# PD_Stepper_V1.net
KiCad netlist of a schematic drawn in Altium Designer
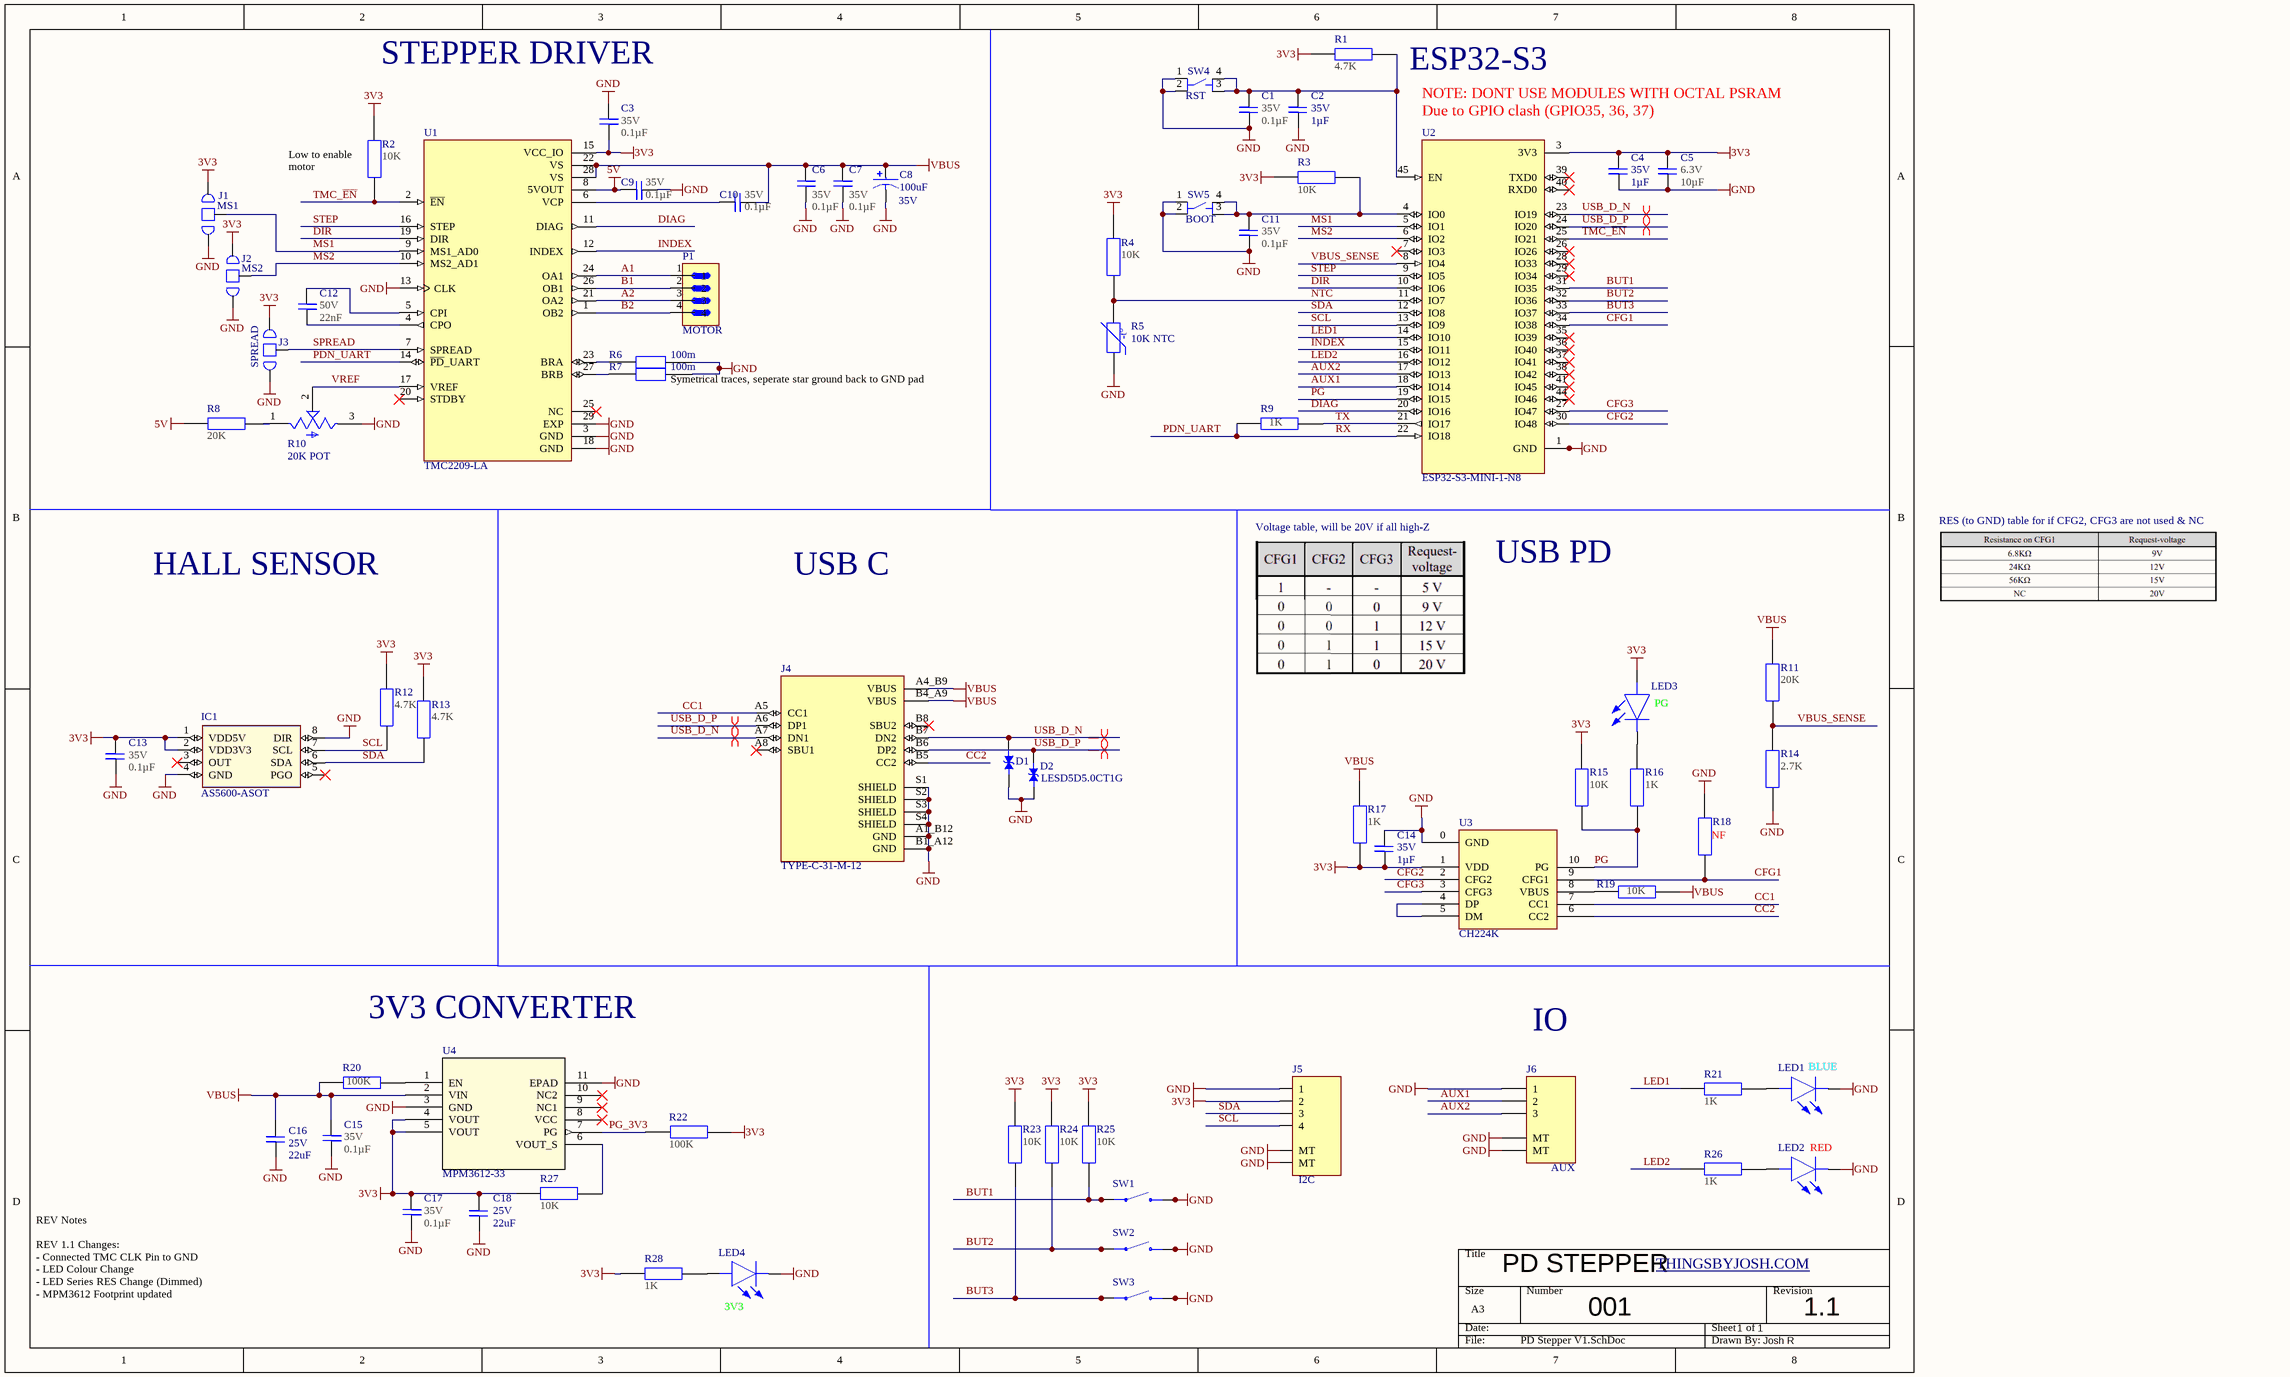
[diagram p0: PD Stepper V1.SchDoc]

(export (version "E")
  (design (tool "Eeschema 10.0.6"))
  (components
    (comp (ref "C1")
      (value "0.1µF")
      (footprint "CAPC1005X55N")
      (description "CAP 0.1µF 35V 0402")
      (fields
        (field (name "MP") "CL05A105KL5NRNC")
        (field (name "MF") "Samsung")
        (field (name "VOLTAGE") "35V")
        (field (name "CHECK_PRICES") "0.1µF")
      )
      (libsource (lib "Custom Library") (part "CL05A105KL5NRNC"))
    )
    (comp (ref "C2")
      (value "1µF ±10% 35V")
      (footprint "CAPC1005X55N")
      (description "CAP 1µF ±10% 35V Ceramic Capacitor X5R 0402 (1005 Metric)")
      (fields
        (field (name "MP") "CL05A105KL5NRNC")
        (field (name "MF") "Samsung")
        (field (name "VOLTAGE") "35V")
        (field (name "CHECK_PRICES") "1µF")
      )
      (libsource (lib "Custom Library") (part "CL05A105KL5NRNC"))
    )
    (comp (ref "C3")
      (value "0.1µF")
      (footprint "CAPC1005X55N")
      (description "CAP 0.1µF 35V 0402")
      (fields
        (field (name "MP") "CL05A105KL5NRNC")
        (field (name "MF") "Samsung")
        (field (name "VOLTAGE") "35V")
        (field (name "CHECK_PRICES") "0.1µF")
      )
      (libsource (lib "Custom Library") (part "CL05A105KL5NRNC"))
    )
    (comp (ref "C4")
      (value "1µF ±10% 35V")
      (footprint "CAPC1005X55N")
      (description "CAP 1µF ±10% 35V Ceramic Capacitor X5R 0402 (1005 Metric)")
      (fields
        (field (name "MP") "CL05A105KL5NRNC")
        (field (name "MF") "Samsung")
        (field (name "VOLTAGE") "35V")
        (field (name "CHECK_PRICES") "1µF")
      )
      (libsource (lib "Custom Library") (part "CL05A105KL5NRNC"))
    )
    (comp (ref "C5")
      (value "10uF 6.3V")
      (footprint "CAPC1005X55N")
      (description "CAP 10µF 6.3V 0402")
      (fields
        (field (name "MP") "CL05A105KL5NRNC")
        (field (name "MF") "Samsung")
        (field (name "VOLTAGE") "6.3V")
        (field (name "CHECK_PRICES") "10µF")
      )
      (libsource (lib "Custom Library") (part "CL05A105KL5NRNC"))
    )
    (comp (ref "C6")
      (value "0.1µF")
      (footprint "CAPC1005X55N")
      (description "CAP 0.1µF 35V 0402")
      (fields
        (field (name "MP") "CL05A105KL5NRNC")
        (field (name "MF") "Samsung")
        (field (name "VOLTAGE") "35V")
        (field (name "CHECK_PRICES") "0.1µF")
      )
      (libsource (lib "Custom Library") (part "CL05A105KL5NRNC"))
    )
    (comp (ref "C7")
      (value "0.1µF")
      (footprint "CAPC1005X55N")
      (description "CAP 0.1µF 35V 0402")
      (fields
        (field (name "MP") "CL05A105KL5NRNC")
        (field (name "MF") "Samsung")
        (field (name "VOLTAGE") "35V")
        (field (name "CHECK_PRICES") "0.1µF")
      )
      (libsource (lib "Custom Library") (part "CL05A105KL5NRNC"))
    )
    (comp (ref "C8")
      (value "100uF")
      (footprint "CAP_EEEFT1V101AP")
      (description "CAP 100µF 35V 260mOhm @ 100kHz 2000 Hrs @ 105°C")
      (fields
        (field (name "MF") "Panasonic")
        (field (name "MP") "EEE-FT1V101AP")
        (field (name "VOLTAGE") "35V")
      )
      (libsource (lib "Custom Library") (part "EEEFT1V101AP"))
    )
    (comp (ref "C9")
      (value "0.1µF")
      (footprint "CAPC1005X55N")
      (description "CAP 0.1µF 35V 0402")
      (fields
        (field (name "MP") "CL05A105KL5NRNC")
        (field (name "MF") "Samsung")
        (field (name "VOLTAGE") "35V")
        (field (name "CHECK_PRICES") "0.1µF")
      )
      (libsource (lib "Custom Library") (part "CL05A105KL5NRNC"))
    )
    (comp (ref "C10")
      (value "0.1µF")
      (footprint "CAPC1005X55N")
      (description "CAP 0.1µF 35V 0402")
      (fields
        (field (name "MP") "CL05A105KL5NRNC")
        (field (name "MF") "Samsung")
        (field (name "VOLTAGE") "35V")
        (field (name "CHECK_PRICES") "0.1µF")
      )
      (libsource (lib "Custom Library") (part "CL05A105KL5NRNC"))
    )
    (comp (ref "C11")
      (value "0.1µF")
      (footprint "CAPC1005X55N")
      (description "CAP 0.1µF 35V 0402")
      (fields
        (field (name "MP") "CL05A105KL5NRNC")
        (field (name "MF") "Samsung")
        (field (name "VOLTAGE") "35V")
        (field (name "CHECK_PRICES") "0.1µF")
      )
      (libsource (lib "Custom Library") (part "CL05A105KL5NRNC"))
    )
    (comp (ref "C12")
      (value "22nF")
      (footprint "CAPC1005X55N")
      (description "CAP 22nF 50V 0402")
      (fields
        (field (name "MP") "CL05A105KL5NRNC")
        (field (name "MF") "Samsung")
        (field (name "VOLTAGE") "50V")
        (field (name "CHECK_PRICES") "22nF")
      )
      (libsource (lib "Custom Library") (part "CL05A105KL5NRNC"))
    )
    (comp (ref "C13")
      (value "0.1µF")
      (footprint "CAPC1005X55N")
      (description "CAP 0.1µF 35V 0402")
      (fields
        (field (name "MP") "CL05A105KL5NRNC")
        (field (name "MF") "Samsung")
        (field (name "VOLTAGE") "35V")
        (field (name "CHECK_PRICES") "0.1µF")
      )
      (libsource (lib "Custom Library") (part "CL05A105KL5NRNC"))
    )
    (comp (ref "C14")
      (value "1µF ±10% 35V")
      (footprint "CAPC1005X55N")
      (description "CAP 1µF ±10% 35V Ceramic Capacitor X5R 0402 (1005 Metric)")
      (fields
        (field (name "MP") "CL05A105KL5NRNC")
        (field (name "MF") "Samsung")
        (field (name "VOLTAGE") "35V")
        (field (name "CHECK_PRICES") "1µF")
      )
      (libsource (lib "Custom Library") (part "CL05A105KL5NRNC"))
    )
    (comp (ref "C15")
      (value "0.1µF")
      (footprint "CAPC1005X55N")
      (description "CAP 0.1µF 35V 0402")
      (fields
        (field (name "MP") "CL05A105KL5NRNC")
        (field (name "MF") "Samsung")
        (field (name "VOLTAGE") "35V")
        (field (name "CHECK_PRICES") "0.1µF")
      )
      (libsource (lib "Custom Library") (part "CL05A105KL5NRNC"))
    )
    (comp (ref "C16")
      (value "22uF")
      (footprint "CAPC2012X135N")
      (description "CAP 22uF 25V")
      (fields
        (field (name "MP") "GRM21BR61E226ME44K")
        (field (name "MF") "Murata Electronics")
        (field (name "VOLTAGE") "25V")
      )
      (libsource (lib "Custom Library") (part "GRM21BR61E226ME44K"))
    )
    (comp (ref "C17")
      (value "0.1µF")
      (footprint "CAPC1005X55N")
      (description "CAP 0.1µF 35V 0402")
      (fields
        (field (name "MP") "CL05A105KL5NRNC")
        (field (name "MF") "Samsung")
        (field (name "VOLTAGE") "35V")
        (field (name "CHECK_PRICES") "0.1µF")
      )
      (libsource (lib "Custom Library") (part "CL05A105KL5NRNC"))
    )
    (comp (ref "C18")
      (value "22uF")
      (footprint "CAPC2012X135N")
      (description "CAP 22uF 25V")
      (fields
        (field (name "MP") "GRM21BR61E226ME44K")
        (field (name "MF") "Murata Electronics")
        (field (name "VOLTAGE") "25V")
      )
      (libsource (lib "Custom Library") (part "GRM21BR61E226ME44K"))
    )
    (comp (ref "D1")
      (value "LESD5D5.0CT1G")
      (footprint "TVS_LESD5D5.0CT1G")
      (description "Transient Voltage Suppressors for ESD Protection")
      (fields (field (name "MF") "Leshan Radio Co."))
      (libsource (lib "Custom Library") (part "LESD5D5.0CT1G"))
    )
    (comp (ref "D2")
      (value "LESD5D5.0CT1G")
      (footprint "TVS_LESD5D5.0CT1G")
      (description "Transient Voltage Suppressors for ESD Protection")
      (fields (field (name "MF") "Leshan Radio Co."))
      (libsource (lib "Custom Library") (part "LESD5D5.0CT1G"))
    )
    (comp (ref "IC1")
      (value "AS5600-ASOT")
      (footprint "SOIC127P600X175-8N")
      (description "Hall Effect Sensor Angle External Magnet, Not Included Gull Wing")
      (fields (field (name "MF") "ams"))
      (libsource (lib "Custom Library") (part "AS5600-ASOT"))
    )
    (comp (ref "J1")
      (value "MS1")
      (footprint "3 way solder jumper")
      (libsource (lib "Custom Library") (part "3 Way Solder Jumper"))
    )
    (comp (ref "J2")
      (value "MS2")
      (footprint "3 way solder jumper")
      (libsource (lib "Custom Library") (part "3 Way Solder Jumper"))
    )
    (comp (ref "J3")
      (value "SPREAD")
      (footprint "3 way solder jumper")
      (libsource (lib "Custom Library") (part "3 Way Solder Jumper"))
    )
    (comp (ref "J4")
      (value "TYPE-C-31-M-12")
      (footprint "HRO_TYPE-C-31-M-12")
      (description "USB Connectors 24 Receptacle 1 8.94*7.3mm RoHS")
      (fields (field (name "MF") "HRO Electronics Co., Ltd."))
      (libsource (lib "Custom Library") (part "TYPE-C-31-M-12"))
    )
    (comp (ref "J5")
      (value "I2C")
      (footprint "JST_SM04B-SRSS-TB(LF)(SN)")
      (description "SH Series 1.0 mm Pitch 2 Position Single Row Side Entry Shrouded Header")
      (fields (field (name "MP") "SM04B-SRSS-TB(LF)(SN)") (field (name "Comment") "JST SH 4P"))
      (libsource (lib "Custom Library") (part "SM04B-SRSS-TB(LF)(SN)"))
    )
    (comp (ref "J6")
      (value "AUX")
      (footprint "JST_SM03B-SRSS-TB(LF)(SN)")
      (description "Connector Header Surface Mount, Right Angle 3 position 0.039 _1.00mm_")
      (fields (field (name "MP") "SM03B-SRSS-TB_LF__SN_") (field (name "MF") "JST Sales"))
      (libsource (lib "Custom Library") (part "SM03B-SRSS-TB(LF)(SN)"))
    )
    (comp (ref "LED1")
      (value "LED BLUE")
      (footprint "LEDC1608X80N")
      (description "BLUE LED Indication - 0603 (1608 Metric)")
      (fields (field (name "MF") "Wurth Electronics") (field (name "MP") "150060GS75000"))
      (libsource (lib "Custom Library") (part "150060GS75000"))
    )
    (comp (ref "LED2")
      (value "LED RED")
      (footprint "LEDC1608X80N")
      (description "RED LED Indication - 0603 (1608 Metric)")
      (fields (field (name "MF") "Wurth Electronics"))
      (libsource (lib "Custom Library") (part "150060GS75000"))
    )
    (comp (ref "LED3")
      (value "LED GREEN")
      (footprint "LEDC1608X80N")
      (description "Green 520nm LED Indication - Discrete 3.2V 0603 (1608 Metric)")
      (fields (field (name "MF") "Wurth Electronics") (field (name "MP") "150060GS75000"))
      (libsource (lib "Custom Library") (part "150060GS75000"))
    )
    (comp (ref "LED4")
      (value "LED GREEN")
      (footprint "LEDC1608X80N")
      (description "Green 520nm LED Indication - Discrete 3.2V 0603 (1608 Metric)")
      (fields (field (name "MF") "Wurth Electronics") (field (name "MP") "150060GS75000"))
      (libsource (lib "Custom Library") (part "150060GS75000"))
    )
    (comp (ref "P1")
      (value "MOTOR")
      (footprint "JST_S4B-PH-SM4-TB")
      (description "Connector Header Surface Mount, Right Angle 4 position 0.079 _2.00mm_")
      (fields (field (name "MF") "JST Sales") (field (name "MP") "S4B-PH-SM4-TB"))
      (libsource (lib "Custom Library") (part "S4B-PH-SM4-TB"))
    )
    (comp (ref "R1")
      (value "4.7K")
      (footprint "RESC1005X37N")
      (description "RES 4.7K 0402")
      (fields (field (name "MP") "AC0402JR-0724KL"))
      (libsource (lib "Custom Library") (part "AC0402JR-0724KL"))
    )
    (comp (ref "R2")
      (value "10K")
      (footprint "RESC1005X37N")
      (description "RES 10K 0402")
      (fields (field (name "MP") "AC0402JR-0724KL"))
      (libsource (lib "Custom Library") (part "AC0402JR-0724KL"))
    )
    (comp (ref "R3")
      (value "10K")
      (footprint "RESC1005X37N")
      (description "RES 10K 0402")
      (fields (field (name "MP") "AC0402JR-0724KL"))
      (libsource (lib "Custom Library") (part "AC0402JR-0724KL"))
    )
    (comp (ref "R4")
      (value "10K")
      (footprint "RESC1005X37N")
      (description "RES 10K 0402")
      (fields (field (name "MP") "AC0402JR-0724KL"))
      (libsource (lib "Custom Library") (part "AC0402JR-0724KL"))
    )
    (comp (ref "R5")
      (value "10K NTC")
      (footprint "NTC Pads")
      (description "NTC 10K")
      (libsource (lib "Custom Library") (part "NTC"))
    )
    (comp (ref "R6")
      (value "100m")
      (footprint "RESC3216X89N")
      (description "Res Metal Foil 1206 100m Ohm 1% 1W Â±100ppm/Â°C Molded SMD Paper T/R")
      (fields (field (name "MP") "PE1206FRF470R1L"))
      (libsource (lib "Custom Library") (part "PE1206FRF470R1L"))
    )
    (comp (ref "R7")
      (value "100m")
      (footprint "RESC3216X89N")
      (description "Res Metal Foil 1206 100m Ohm 1% 1W Â±100ppm/Â°C Molded SMD Paper T/R")
      (fields (field (name "MP") "PE1206FRF470R1L"))
      (libsource (lib "Custom Library") (part "PE1206FRF470R1L"))
    )
    (comp (ref "R8")
      (value "20K")
      (footprint "RESC1005X37N")
      (description "RES 20K 0402")
      (fields (field (name "MP") "AC0402JR-0724KL"))
      (libsource (lib "Custom Library") (part "AC0402JR-0724KL"))
    )
    (comp (ref "R9")
      (value "1K")
      (footprint "RESC1005X37N")
      (description "RES 1K 0402")
      (fields (field (name "MP") "AC0402JR-0724KL"))
      (libsource (lib "Custom Library") (part "AC0402JR-0724KL"))
    )
    (comp (ref "R10")
      (value "20K POT")
      (footprint "TRIM_TC33X-2-203E")
      (description "20k Ohms 0.1W, 1/10W J Lead Surface Mount Trimmer Potentiometer Cermet 1 Turn Top Adjustment")
      (fields (field (name "MF") "Bourns") (field (name "DIGI-KEY_PART_NUMBER") "TC33X-2-203ECT-ND"))
      (libsource (lib "Custom Library") (part "TC33X-2-203E"))
    )
    (comp (ref "R11")
      (value "20K")
      (footprint "RESC1005X37N")
      (description "RES 20K 0402")
      (fields (field (name "MP") "AC0402JR-0724KL"))
      (libsource (lib "Custom Library") (part "AC0402JR-0724KL"))
    )
    (comp (ref "R12")
      (value "4.7K")
      (footprint "RESC1005X37N")
      (description "RES 4.7K 0402")
      (fields (field (name "MP") "AC0402JR-0724KL"))
      (libsource (lib "Custom Library") (part "AC0402JR-0724KL"))
    )
    (comp (ref "R13")
      (value "4.7K")
      (footprint "RESC1005X37N")
      (description "RES 4.7K 0402")
      (fields (field (name "MP") "AC0402JR-0724KL"))
      (libsource (lib "Custom Library") (part "AC0402JR-0724KL"))
    )
    (comp (ref "R14")
      (value "2.7K")
      (footprint "RESC1005X37N")
      (description "RES 2.7K 0402")
      (fields (field (name "MP") "AC0402JR-0724KL"))
      (libsource (lib "Custom Library") (part "AC0402JR-0724KL"))
    )
    (comp (ref "R15")
      (value "10K")
      (footprint "RESC1005X37N")
      (description "RES 10K 0402")
      (fields (field (name "MP") "AC0402JR-0724KL"))
      (libsource (lib "Custom Library") (part "AC0402JR-0724KL"))
    )
    (comp (ref "R16")
      (value "1K")
      (footprint "RESC1005X37N")
      (description "RES 1K 0402")
      (fields (field (name "MP") "AC0402JR-0724KL"))
      (libsource (lib "Custom Library") (part "AC0402JR-0724KL"))
    )
    (comp (ref "R17")
      (value "1K")
      (footprint "RESC1005X37N")
      (description "RES 1K 0402")
      (fields (field (name "MP") "AC0402JR-0724KL"))
      (libsource (lib "Custom Library") (part "AC0402JR-0724KL"))
    )
    (comp (ref "R18")
      (value "NF")
      (footprint "RESC1005X37N")
      (description "RES NC")
      (fields (field (name "MP") "AC0402JR-0724KL"))
      (libsource (lib "Custom Library") (part "AC0402JR-0724KL"))
    )
    (comp (ref "R19")
      (value "10K")
      (footprint "RESC1005X37N")
      (description "RES 10K 0402")
      (fields (field (name "MP") "AC0402JR-0724KL"))
      (libsource (lib "Custom Library") (part "AC0402JR-0724KL"))
    )
    (comp (ref "R20")
      (value "100K")
      (footprint "RESC1005X37N")
      (description "RES 100K 0402")
      (fields (field (name "MP") "AC0402JR-0724KL"))
      (libsource (lib "Custom Library") (part "AC0402JR-0724KL"))
    )
    (comp (ref "R21")
      (value "1K")
      (footprint "RESC1005X37N")
      (description "RES 1K 0402")
      (fields (field (name "MP") "AC0402JR-0724KL"))
      (libsource (lib "Custom Library") (part "AC0402JR-0724KL"))
    )
    (comp (ref "R22")
      (value "100K")
      (footprint "RESC1005X37N")
      (description "RES 100K 0402")
      (fields (field (name "MP") "AC0402JR-0724KL"))
      (libsource (lib "Custom Library") (part "AC0402JR-0724KL"))
    )
    (comp (ref "R23")
      (value "10K")
      (footprint "RESC1005X37N")
      (description "RES 10K 0402")
      (fields (field (name "MP") "AC0402JR-0724KL"))
      (libsource (lib "Custom Library") (part "AC0402JR-0724KL"))
    )
    (comp (ref "R24")
      (value "10K")
      (footprint "RESC1005X37N")
      (description "RES 10K 0402")
      (fields (field (name "MP") "AC0402JR-0724KL"))
      (libsource (lib "Custom Library") (part "AC0402JR-0724KL"))
    )
    (comp (ref "R25")
      (value "10K")
      (footprint "RESC1005X37N")
      (description "RES 10K 0402")
      (fields (field (name "MP") "AC0402JR-0724KL"))
      (libsource (lib "Custom Library") (part "AC0402JR-0724KL"))
    )
    (comp (ref "R26")
      (value "1K")
      (footprint "RESC1005X37N")
      (description "RES 1K 0402")
      (fields (field (name "MP") "AC0402JR-0724KL"))
      (libsource (lib "Custom Library") (part "AC0402JR-0724KL"))
    )
    (comp (ref "R27")
      (value "10K")
      (footprint "RESC1005X37N")
      (description "RES 10K 0402")
      (fields (field (name "MP") "AC0402JR-0724KL"))
      (libsource (lib "Custom Library") (part "AC0402JR-0724KL"))
    )
    (comp (ref "R28")
      (value "1K")
      (footprint "RESC1005X37N")
      (description "RES 1K 0402")
      (fields (field (name "MP") "AC0402JR-0724KL"))
      (libsource (lib "Custom Library") (part "AC0402JR-0724KL"))
    )
    (comp (ref "SW1")
      (value "EVQ-P7J01P")
      (footprint "SW_EVQ-P7J01P")
      (description "Tactile Switch SPST-NO Side Actuated Surface Mount, Right Angle")
      (fields (field (name "MF") "Panasonic Electronic"))
      (libsource (lib "Custom Library") (part "EVQ-P7J01P"))
    )
    (comp (ref "SW2")
      (value "EVQ-P7J01P")
      (footprint "SW_EVQ-P7J01P")
      (description "Tactile Switch SPST-NO Side Actuated Surface Mount, Right Angle")
      (fields (field (name "MF") "Panasonic Electronic"))
      (libsource (lib "Custom Library") (part "EVQ-P7J01P"))
    )
    (comp (ref "SW3")
      (value "EVQ-P7J01P")
      (footprint "SW_EVQ-P7J01P")
      (description "Tactile Switch SPST-NO Side Actuated Surface Mount, Right Angle")
      (fields (field (name "MF") "Panasonic Electronic"))
      (libsource (lib "Custom Library") (part "EVQ-P7J01P"))
    )
    (comp (ref "SW4")
      (value "PTS810_SJM_250_SMTR_LFS")
      (footprint "SW_PTS810_SJM_250_SMTR_LFS")
      (description "Tactile Switch SPST-NO Top Actuated Surface Mount")
      (fields (field (name "MF") "C&K") (field (name "MP") "PTS810 SJM 250 SMTR LFS"))
      (libsource (lib "Custom Library") (part "PTS810_SJM_250_SMTR_LFS"))
    )
    (comp (ref "SW5")
      (value "PTS810_SJM_250_SMTR_LFS")
      (footprint "SW_PTS810_SJM_250_SMTR_LFS")
      (description "Tactile Switch SPST-NO Top Actuated Surface Mount")
      (fields (field (name "MF") "C&K") (field (name "MP") "PTS810 SJM 250 SMTR LFS"))
      (libsource (lib "Custom Library") (part "PTS810_SJM_250_SMTR_LFS"))
    )
    (comp (ref "U1")
      (value "TMC2209-LA")
      (footprint "QFN50P500X500X90-29N")
      (fields (field (name "MF") "Trinamic"))
      (libsource (lib "Custom Library") (part "TMC2209-LA"))
    )
    (comp (ref "U2")
      (value "ESP32-S3-MINI-1-N8")
      (footprint "XCVR_ESP32-S3-MINI-1-N8")
      (description "Bluetooth, WiFi 802.11b/g/n, Bluetooth v5.0 Transceiver Module 2.4GHz PCB Trace Surface Mount")
      (fields (field (name "MF") "Espressif Systems"))
      (libsource (lib "Custom Library") (part "ESP32-S3-MINI-1-N8"))
    )
    (comp (ref "U3")
      (value "CH224K")
      (footprint "ESSOP-10")
      (description "USB PD Sink Controller")
      (libsource (lib "Custom Library") (part "CH224K"))
    )
    (comp (ref "U4")
      (value "MPM3612-33")
      (footprint "LGA_MPM3612_MNP")
      (libsource (lib "Custom Library") (part "MPM3612-33"))
    )
  )
  (nets
    (net (code "1") (name "/A1") (class "Default")
      (node (ref "P1") (pin "1") (pinfunction "1_1") (pintype "passive"))
      (node (ref "U1") (pin "24") (pinfunction "OA1_24") (pintype "output"))
    )
    (net (code "2") (name "/A2") (class "Default")
      (node (ref "P1") (pin "3") (pinfunction "3_3") (pintype "passive"))
      (node (ref "U1") (pin "21") (pinfunction "OA2_21") (pintype "output"))
    )
    (net (code "3") (name "/AUX1") (class "Default")
      (node (ref "J6") (pin "2") (pinfunction "2_2") (pintype "passive"))
      (node (ref "U2") (pin "18") (pinfunction "IO14_18") (pintype "bidirectional"))
    )
    (net (code "4") (name "/AUX2") (class "Default")
      (node (ref "J6") (pin "3") (pinfunction "3_3") (pintype "passive"))
      (node (ref "U2") (pin "17") (pinfunction "IO13_17") (pintype "bidirectional"))
    )
    (net (code "5") (name "/B1") (class "Default")
      (node (ref "P1") (pin "2") (pinfunction "2_2") (pintype "passive"))
      (node (ref "U1") (pin "26") (pinfunction "OB1_26") (pintype "output"))
    )
    (net (code "6") (name "/B2") (class "Default")
      (node (ref "P1") (pin "4") (pinfunction "4_4") (pintype "passive"))
      (node (ref "U1") (pin "1") (pinfunction "OB2_1") (pintype "output"))
    )
    (net (code "7") (name "/BUT1") (class "Default")
      (node (ref "R25") (pin "1") (pinfunction "1_1") (pintype "passive"))
      (node (ref "SW1") (pin "1_1") (pinfunction "1_1_1") (pintype "passive"))
      (node (ref "SW1") (pin "1_2") (pinfunction "1_1_2") (pintype "passive"))
      (node (ref "U2") (pin "31") (pinfunction "IO35_31") (pintype "bidirectional"))
    )
    (net (code "8") (name "/BUT2") (class "Default")
      (node (ref "R24") (pin "1") (pinfunction "1_1") (pintype "passive"))
      (node (ref "SW2") (pin "1_1") (pinfunction "1_1_1") (pintype "passive"))
      (node (ref "SW2") (pin "1_2") (pinfunction "1_1_2") (pintype "passive"))
      (node (ref "U2") (pin "32") (pinfunction "IO36_32") (pintype "bidirectional"))
    )
    (net (code "9") (name "/BUT3") (class "Default")
      (node (ref "R23") (pin "1") (pinfunction "1_1") (pintype "passive"))
      (node (ref "SW3") (pin "1_1") (pinfunction "1_1_1") (pintype "passive"))
      (node (ref "SW3") (pin "1_2") (pinfunction "1_1_2") (pintype "passive"))
      (node (ref "U2") (pin "33") (pinfunction "IO37_33") (pintype "bidirectional"))
    )
    (net (code "10") (name "/CC1") (class "Default")
      (node (ref "J4") (pin "A5") (pinfunction "CC1_A5") (pintype "bidirectional"))
      (node (ref "U3") (pin "7") (pinfunction "CC1_7") (pintype "passive"))
    )
    (net (code "11") (name "/CC2") (class "Default")
      (node (ref "J4") (pin "B5") (pinfunction "CC2_B5") (pintype "bidirectional"))
      (node (ref "U3") (pin "6") (pinfunction "CC2_6") (pintype "passive"))
    )
    (net (code "12") (name "/CFG1") (class "Default")
      (node (ref "R18") (pin "1") (pinfunction "1_1") (pintype "passive"))
      (node (ref "U2") (pin "34") (pinfunction "IO38_34") (pintype "bidirectional"))
      (node (ref "U3") (pin "9") (pinfunction "CFG1_9") (pintype "passive"))
    )
    (net (code "13") (name "/CFG2") (class "Default")
      (node (ref "U2") (pin "30") (pinfunction "IO48_30") (pintype "bidirectional"))
      (node (ref "U3") (pin "2") (pinfunction "CFG2_2") (pintype "passive"))
    )
    (net (code "14") (name "/CFG3") (class "Default")
      (node (ref "U2") (pin "27") (pinfunction "IO47_27") (pintype "bidirectional"))
      (node (ref "U3") (pin "3") (pinfunction "CFG3_3") (pintype "passive"))
    )
    (net (code "15") (name "/DIAG") (class "Default")
      (node (ref "U1") (pin "11") (pinfunction "DIAG_11") (pintype "output"))
      (node (ref "U2") (pin "20") (pinfunction "IO16_20") (pintype "bidirectional"))
    )
    (net (code "16") (name "/DIR") (class "Default")
      (node (ref "U1") (pin "19") (pinfunction "DIR_19") (pintype "input"))
      (node (ref "U2") (pin "10") (pinfunction "IO6_10") (pintype "bidirectional"))
    )
    (net (code "17") (name "/INDEX") (class "Default")
      (node (ref "U1") (pin "12") (pinfunction "INDEX_12") (pintype "output"))
      (node (ref "U2") (pin "15") (pinfunction "IO11_15") (pintype "bidirectional"))
    )
    (net (code "18") (name "/LED1") (class "Default")
      (node (ref "R21") (pin "2") (pinfunction "2_2") (pintype "passive"))
      (node (ref "U2") (pin "14") (pinfunction "IO10_14") (pintype "bidirectional"))
    )
    (net (code "19") (name "/LED2") (class "Default")
      (node (ref "R26") (pin "2") (pinfunction "2_2") (pintype "passive"))
      (node (ref "U2") (pin "16") (pinfunction "IO12_16") (pintype "bidirectional"))
    )
    (net (code "20") (name "/MS1") (class "Default")
      (node (ref "J1") (pin "2") (pinfunction "2_2") (pintype "passive"))
      (node (ref "U1") (pin "9") (pinfunction "MS1_AD0_9") (pintype "input"))
      (node (ref "U2") (pin "5") (pinfunction "IO1_5") (pintype "bidirectional"))
    )
    (net (code "21") (name "/MS2") (class "Default")
      (node (ref "J2") (pin "2") (pinfunction "2_2") (pintype "passive"))
      (node (ref "U1") (pin "10") (pinfunction "MS2_AD1_10") (pintype "input"))
      (node (ref "U2") (pin "6") (pinfunction "IO2_6") (pintype "bidirectional"))
    )
    (net (code "22") (name "/NTC") (class "Default")
      (node (ref "R4") (pin "2") (pinfunction "2_2") (pintype "passive"))
      (node (ref "R5") (pin "2") (pinfunction "2_2") (pintype "passive"))
      (node (ref "U2") (pin "11") (pinfunction "IO7_11") (pintype "bidirectional"))
    )
    (net (code "23") (name "/PDN_UART") (class "Default")
      (node (ref "R9") (pin "2") (pinfunction "2_2") (pintype "passive"))
      (node (ref "U1") (pin "14") (pinfunction "~{PD}_UART_14") (pintype "bidirectional"))
      (node (ref "U2") (pin "22") (pinfunction "IO18_22") (pintype "input"))
    )
    (net (code "24") (name "/PG") (class "Default")
      (node (ref "R15") (pin "1") (pinfunction "1_1") (pintype "passive"))
      (node (ref "R16") (pin "1") (pinfunction "1_1") (pintype "passive"))
      (node (ref "U2") (pin "19") (pinfunction "IO15_19") (pintype "bidirectional"))
      (node (ref "U3") (pin "10") (pinfunction "PG_10") (pintype "passive"))
    )
    (net (code "25") (name "/PG_3V3") (class "Default")
      (node (ref "R22") (pin "1") (pinfunction "1_1") (pintype "passive"))
      (node (ref "U4") (pin "7") (pinfunction "PG_7") (pintype "output"))
    )
    (net (code "26") (name "/SCL") (class "Default")
      (node (ref "IC1") (pin "7") (pinfunction "SCL_7") (pintype "bidirectional"))
      (node (ref "J5") (pin "4") (pinfunction "4_4") (pintype "passive"))
      (node (ref "R12") (pin "1") (pinfunction "1_1") (pintype "passive"))
      (node (ref "U2") (pin "13") (pinfunction "IO9_13") (pintype "bidirectional"))
    )
    (net (code "27") (name "/SDA") (class "Default")
      (node (ref "IC1") (pin "6") (pinfunction "SDA_6") (pintype "bidirectional"))
      (node (ref "J5") (pin "3") (pinfunction "3_3") (pintype "passive"))
      (node (ref "R13") (pin "1") (pinfunction "1_1") (pintype "passive"))
      (node (ref "U2") (pin "12") (pinfunction "IO8_12") (pintype "bidirectional"))
    )
    (net (code "28") (name "/SPREAD") (class "Default")
      (node (ref "J3") (pin "2") (pinfunction "2_2") (pintype "passive"))
      (node (ref "U1") (pin "7") (pinfunction "SPREAD_7") (pintype "input"))
    )
    (net (code "29") (name "/STEP") (class "Default")
      (node (ref "U1") (pin "16") (pinfunction "STEP_16") (pintype "input"))
      (node (ref "U2") (pin "9") (pinfunction "IO5_9") (pintype "bidirectional"))
    )
    (net (code "30") (name "/TMC_~{EN}") (class "Default")
      (node (ref "R2") (pin "1") (pinfunction "1_1") (pintype "passive"))
      (node (ref "U1") (pin "2") (pinfunction "~{EN}_2") (pintype "input"))
      (node (ref "U2") (pin "25") (pinfunction "IO21_25") (pintype "bidirectional"))
    )
    (net (code "31") (name "/TX") (class "Default")
      (node (ref "R9") (pin "1") (pinfunction "1_1") (pintype "passive"))
      (node (ref "U2") (pin "21") (pinfunction "IO17_21") (pintype "output"))
    )
    (net (code "32") (name "/USB_D_N") (class "Default")
      (node (ref "D1") (pin "2") (pinfunction "2_2") (pintype "passive"))
      (node (ref "J4") (pin "A7") (pinfunction "DN1_A7") (pintype "bidirectional"))
      (node (ref "J4") (pin "B7") (pinfunction "DN2_B7") (pintype "bidirectional"))
      (node (ref "U2") (pin "23") (pinfunction "IO19_23") (pintype "bidirectional"))
    )
    (net (code "33") (name "/USB_D_P") (class "Default")
      (node (ref "D2") (pin "2") (pinfunction "2_2") (pintype "passive"))
      (node (ref "J4") (pin "A6") (pinfunction "DP1_A6") (pintype "bidirectional"))
      (node (ref "J4") (pin "B6") (pinfunction "DP2_B6") (pintype "bidirectional"))
      (node (ref "U2") (pin "24") (pinfunction "IO20_24") (pintype "bidirectional"))
    )
    (net (code "34") (name "/VBUS_SENSE") (class "Default")
      (node (ref "R11") (pin "1") (pinfunction "1_1") (pintype "passive"))
      (node (ref "R14") (pin "2") (pinfunction "2_2") (pintype "passive"))
      (node (ref "U2") (pin "8") (pinfunction "IO4_8") (pintype "input"))
    )
    (net (code "35") (name "/VREF") (class "Default")
      (node (ref "R10") (pin "2") (pinfunction "W_2") (pintype "passive"))
      (node (ref "U1") (pin "17") (pinfunction "VREF_17") (pintype "input"))
    )
    (net (code "36") (name "3V3") (class "Default")
      (node (ref "C13") (pin "1") (pinfunction "1_1") (pintype "passive"))
      (node (ref "C14") (pin "2") (pinfunction "2_2") (pintype "passive"))
      (node (ref "C17") (pin "2") (pinfunction "2_2") (pintype "passive"))
      (node (ref "C18") (pin "1") (pinfunction "1_1") (pintype "passive"))
      (node (ref "C3") (pin "1") (pinfunction "1_1") (pintype "passive"))
      (node (ref "C4") (pin "1") (pinfunction "1_1") (pintype "passive"))
      (node (ref "C5") (pin "1") (pinfunction "1_1") (pintype "passive"))
      (node (ref "IC1") (pin "1") (pinfunction "VDD5V_1") (pintype "bidirectional"))
      (node (ref "IC1") (pin "2") (pinfunction "VDD3V3_2") (pintype "bidirectional"))
      (node (ref "J1") (pin "1") (pinfunction "12_1") (pintype "passive"))
      (node (ref "J2") (pin "1") (pinfunction "12_1") (pintype "passive"))
      (node (ref "J3") (pin "1") (pinfunction "12_1") (pintype "passive"))
      (node (ref "J5") (pin "2") (pinfunction "2_2") (pintype "passive"))
      (node (ref "LED3") (pin "2") (pinfunction "A_2") (pintype "passive"))
      (node (ref "R1") (pin "2") (pinfunction "2_2") (pintype "passive"))
      (node (ref "R12") (pin "2") (pinfunction "2_2") (pintype "passive"))
      (node (ref "R13") (pin "2") (pinfunction "2_2") (pintype "passive"))
      (node (ref "R15") (pin "2") (pinfunction "2_2") (pintype "passive"))
      (node (ref "R17") (pin "1") (pinfunction "1_1") (pintype "passive"))
      (node (ref "R2") (pin "2") (pinfunction "2_2") (pintype "passive"))
      (node (ref "R22") (pin "2") (pinfunction "2_2") (pintype "passive"))
      (node (ref "R23") (pin "2") (pinfunction "2_2") (pintype "passive"))
      (node (ref "R24") (pin "2") (pinfunction "2_2") (pintype "passive"))
      (node (ref "R25") (pin "2") (pinfunction "2_2") (pintype "passive"))
      (node (ref "R27") (pin "2") (pinfunction "2_2") (pintype "passive"))
      (node (ref "R28") (pin "2") (pinfunction "2_2") (pintype "passive"))
      (node (ref "R3") (pin "2") (pinfunction "2_2") (pintype "passive"))
      (node (ref "R4") (pin "1") (pinfunction "1_1") (pintype "passive"))
      (node (ref "U1") (pin "15") (pinfunction "VCC_IO_15") (pintype "power_in"))
      (node (ref "U2") (pin "3") (pinfunction "3V3_3") (pintype "power_in"))
      (node (ref "U3") (pin "1") (pinfunction "VDD_1") (pintype "passive"))
      (node (ref "U4") (pin "4") (pinfunction "VOUT_4") (pintype "power_in"))
      (node (ref "U4") (pin "5") (pinfunction "VOUT_5") (pintype "power_in"))
    )
    (net (code "37") (name "5V") (class "Default")
      (node (ref "C9") (pin "1") (pinfunction "1_1") (pintype "passive"))
      (node (ref "R8") (pin "2") (pinfunction "2_2") (pintype "passive"))
      (node (ref "U1") (pin "8") (pinfunction "5VOUT_8") (pintype "power_in"))
    )
    (net (code "38") (name "GND") (class "Default")
      (node (ref "C1") (pin "2") (pinfunction "2_2") (pintype "passive"))
      (node (ref "C11") (pin "2") (pinfunction "2_2") (pintype "passive"))
      (node (ref "C13") (pin "2") (pinfunction "2_2") (pintype "passive"))
      (node (ref "C14") (pin "1") (pinfunction "1_1") (pintype "passive"))
      (node (ref "C15") (pin "1") (pinfunction "1_1") (pintype "passive"))
      (node (ref "C16") (pin "2") (pinfunction "2_2") (pintype "passive"))
      (node (ref "C17") (pin "1") (pinfunction "1_1") (pintype "passive"))
      (node (ref "C18") (pin "2") (pinfunction "2_2") (pintype "passive"))
      (node (ref "C2") (pin "2") (pinfunction "2_2") (pintype "passive"))
      (node (ref "C3") (pin "2") (pinfunction "2_2") (pintype "passive"))
      (node (ref "C4") (pin "2") (pinfunction "2_2") (pintype "passive"))
      (node (ref "C5") (pin "2") (pinfunction "2_2") (pintype "passive"))
      (node (ref "C6") (pin "1") (pinfunction "1_1") (pintype "passive"))
      (node (ref "C7") (pin "1") (pinfunction "1_1") (pintype "passive"))
      (node (ref "C8") (pin "2") (pinfunction "2_2") (pintype "passive"))
      (node (ref "C9") (pin "2") (pinfunction "2_2") (pintype "passive"))
      (node (ref "D1") (pin "1") (pinfunction "1_1") (pintype "passive"))
      (node (ref "D2") (pin "1") (pinfunction "1_1") (pintype "passive"))
      (node (ref "IC1") (pin "4") (pinfunction "GND_4") (pintype "bidirectional"))
      (node (ref "IC1") (pin "8") (pinfunction "DIR_8") (pintype "bidirectional"))
      (node (ref "J1") (pin "3") (pinfunction "3_3") (pintype "passive"))
      (node (ref "J2") (pin "3") (pinfunction "3_3") (pintype "passive"))
      (node (ref "J3") (pin "3") (pinfunction "3_3") (pintype "passive"))
      (node (ref "J4") (pin "A1_B12") (pinfunction "GND_A1_B12") (pintype "power_in"))
      (node (ref "J4") (pin "B1_A12") (pinfunction "GND_B1_A12") (pintype "power_in"))
      (node (ref "J4") (pin "S1") (pinfunction "SHIELD_S1") (pintype "passive"))
      (node (ref "J4") (pin "S2") (pinfunction "SHIELD_S2") (pintype "passive"))
      (node (ref "J4") (pin "S3") (pinfunction "SHIELD_S3") (pintype "passive"))
      (node (ref "J4") (pin "S4") (pinfunction "SHIELD_S4") (pintype "passive"))
      (node (ref "J5") (pin "1") (pinfunction "1_1") (pintype "passive"))
      (node (ref "J5") (pin "S1") (pinfunction "MT_S1") (pintype "passive"))
      (node (ref "J5") (pin "S2") (pinfunction "MT_S2") (pintype "passive"))
      (node (ref "J6") (pin "1") (pinfunction "1_1") (pintype "passive"))
      (node (ref "J6") (pin "S1") (pinfunction "MT_S1") (pintype "passive"))
      (node (ref "J6") (pin "S2") (pinfunction "MT_S2") (pintype "passive"))
      (node (ref "LED1") (pin "1") (pinfunction "K_1") (pintype "passive"))
      (node (ref "LED2") (pin "1") (pinfunction "K_1") (pintype "passive"))
      (node (ref "LED4") (pin "1") (pinfunction "K_1") (pintype "passive"))
      (node (ref "R10") (pin "3") (pinfunction "CW_3") (pintype "passive"))
      (node (ref "R14") (pin "1") (pinfunction "1_1") (pintype "passive"))
      (node (ref "R18") (pin "2") (pinfunction "2_2") (pintype "passive"))
      (node (ref "R5") (pin "1") (pinfunction "1_1") (pintype "passive"))
      (node (ref "R6") (pin "2") (pinfunction "2_2") (pintype "passive"))
      (node (ref "R7") (pin "2") (pinfunction "2_2") (pintype "passive"))
      (node (ref "SW1") (pin "2_1") (pinfunction "2_2_1") (pintype "passive"))
      (node (ref "SW1") (pin "2_2") (pinfunction "2_2_2") (pintype "passive"))
      (node (ref "SW2") (pin "2_1") (pinfunction "2_2_1") (pintype "passive"))
      (node (ref "SW2") (pin "2_2") (pinfunction "2_2_2") (pintype "passive"))
      (node (ref "SW3") (pin "2_1") (pinfunction "2_2_1") (pintype "passive"))
      (node (ref "SW3") (pin "2_2") (pinfunction "2_2_2") (pintype "passive"))
      (node (ref "SW4") (pin "1") (pinfunction "1_1") (pintype "passive"))
      (node (ref "SW4") (pin "2") (pinfunction "2_2") (pintype "passive"))
      (node (ref "SW5") (pin "1") (pinfunction "1_1") (pintype "passive"))
      (node (ref "SW5") (pin "2") (pinfunction "2_2") (pintype "passive"))
      (node (ref "U1") (pin "13") (pinfunction "CLK_13") (pintype "input"))
      (node (ref "U1") (pin "18") (pinfunction "GND_18") (pintype "power_in"))
      (node (ref "U1") (pin "29") (pinfunction "EXP_29") (pintype "power_in"))
      (node (ref "U1") (pin "3") (pinfunction "GND_3") (pintype "power_in"))
      (node (ref "U2") (pin "1") (pinfunction "GND_1") (pintype "power_in"))
      (node (ref "U2") (pin "2") (pinfunction "GND_2") (pintype "power_in"))
      (node (ref "U2") (pin "42") (pinfunction "GND_42") (pintype "power_in"))
      (node (ref "U2") (pin "43") (pinfunction "GND_43") (pintype "power_in"))
      (node (ref "U2") (pin "46") (pinfunction "GND_46") (pintype "power_in"))
      (node (ref "U2") (pin "47") (pinfunction "GND_47") (pintype "power_in"))
      (node (ref "U2") (pin "48") (pinfunction "GND_48") (pintype "power_in"))
      (node (ref "U2") (pin "49") (pinfunction "GND_49") (pintype "power_in"))
      (node (ref "U2") (pin "50") (pinfunction "GND_50") (pintype "power_in"))
      (node (ref "U2") (pin "51") (pinfunction "GND_51") (pintype "power_in"))
      (node (ref "U2") (pin "52") (pinfunction "GND_52") (pintype "power_in"))
      (node (ref "U2") (pin "53") (pinfunction "GND_53") (pintype "power_in"))
      (node (ref "U2") (pin "54") (pinfunction "GND_54") (pintype "power_in"))
      (node (ref "U2") (pin "55") (pinfunction "GND_55") (pintype "power_in"))
      (node (ref "U2") (pin "56") (pinfunction "GND_56") (pintype "power_in"))
      (node (ref "U2") (pin "57") (pinfunction "GND_57") (pintype "power_in"))
      (node (ref "U2") (pin "58") (pinfunction "GND_58") (pintype "power_in"))
      (node (ref "U2") (pin "59") (pinfunction "GND_59") (pintype "power_in"))
      (node (ref "U2") (pin "60") (pinfunction "GND_60") (pintype "power_in"))
      (node (ref "U2") (pin "61") (pinfunction "GND_61") (pintype "power_in"))
      (node (ref "U2") (pin "61_1") (pinfunction "GND_61_1") (pintype "power_in"))
      (node (ref "U2") (pin "61_2") (pinfunction "GND_61_2") (pintype "power_in"))
      (node (ref "U2") (pin "61_3") (pinfunction "GND_61_3") (pintype "power_in"))
      (node (ref "U2") (pin "61_4") (pinfunction "GND_61_4") (pintype "power_in"))
      (node (ref "U2") (pin "61_5") (pinfunction "GND_61_5") (pintype "power_in"))
      (node (ref "U2") (pin "61_6") (pinfunction "GND_61_6") (pintype "power_in"))
      (node (ref "U2") (pin "61_7") (pinfunction "GND_61_7") (pintype "power_in"))
      (node (ref "U2") (pin "61_8") (pinfunction "GND_61_8") (pintype "power_in"))
      (node (ref "U2") (pin "62") (pinfunction "GND_62") (pintype "power_in"))
      (node (ref "U2") (pin "63") (pinfunction "GND_63") (pintype "power_in"))
      (node (ref "U2") (pin "64") (pinfunction "GND_64") (pintype "power_in"))
      (node (ref "U2") (pin "65") (pinfunction "GND_65") (pintype "power_in"))
      (node (ref "U3") (pin "0") (pinfunction "GND_0") (pintype "passive"))
      (node (ref "U4") (pin "11") (pinfunction "EPAD_11") (pintype "power_in"))
      (node (ref "U4") (pin "3") (pinfunction "GND_3") (pintype "power_in"))
    )
    (net (code "39") (name "Net-(LED1-A)") (class "Default")
      (node (ref "LED1") (pin "2") (pinfunction "A_2") (pintype "passive"))
      (node (ref "R21") (pin "1") (pinfunction "1_1") (pintype "passive"))
    )
    (net (code "40") (name "Net-(LED2-A)") (class "Default")
      (node (ref "LED2") (pin "2") (pinfunction "A_2") (pintype "passive"))
      (node (ref "R26") (pin "1") (pinfunction "1_1") (pintype "passive"))
    )
    (net (code "41") (name "Net-(LED3-K)") (class "Default")
      (node (ref "LED3") (pin "1") (pinfunction "K_1") (pintype "passive"))
      (node (ref "R16") (pin "2") (pinfunction "2_2") (pintype "passive"))
    )
    (net (code "42") (name "Net-(LED4-A)") (class "Default")
      (node (ref "LED4") (pin "2") (pinfunction "A_2") (pintype "passive"))
      (node (ref "R28") (pin "1") (pinfunction "1_1") (pintype "passive"))
    )
    (net (code "43") (name "Net-(R10-CCW)") (class "Default")
      (node (ref "R10") (pin "1") (pinfunction "CCW_1") (pintype "passive"))
      (node (ref "R8") (pin "1") (pinfunction "1_1") (pintype "passive"))
    )
    (net (code "44") (name "Net-(U1-BRA)") (class "Default")
      (node (ref "R6") (pin "1") (pinfunction "1_1") (pintype "passive"))
      (node (ref "U1") (pin "23") (pinfunction "BRA_23") (pintype "bidirectional"))
    )
    (net (code "45") (name "Net-(U1-BRB)") (class "Default")
      (node (ref "R7") (pin "1") (pinfunction "1_1") (pintype "passive"))
      (node (ref "U1") (pin "27") (pinfunction "BRB_27") (pintype "bidirectional"))
    )
    (net (code "46") (name "Net-(U1-CPI)") (class "Default")
      (node (ref "C12") (pin "2") (pinfunction "2_2") (pintype "passive"))
      (node (ref "U1") (pin "5") (pinfunction "CPI_5") (pintype "input"))
    )
    (net (code "47") (name "Net-(U1-CPO)") (class "Default")
      (node (ref "C12") (pin "1") (pinfunction "1_1") (pintype "passive"))
      (node (ref "U1") (pin "4") (pinfunction "CPO_4") (pintype "output"))
    )
    (net (code "48") (name "Net-(U1-VCP)") (class "Default")
      (node (ref "C10") (pin "1") (pinfunction "1_1") (pintype "passive"))
      (node (ref "U1") (pin "6") (pinfunction "VCP_6") (pintype "power_in"))
    )
    (net (code "49") (name "Net-(U2-EN)") (class "Default")
      (node (ref "C1") (pin "1") (pinfunction "1_1") (pintype "passive"))
      (node (ref "C2") (pin "1") (pinfunction "1_1") (pintype "passive"))
      (node (ref "R1") (pin "1") (pinfunction "1_1") (pintype "passive"))
      (node (ref "SW4") (pin "3") (pinfunction "3_3") (pintype "passive"))
      (node (ref "SW4") (pin "4") (pinfunction "4_4") (pintype "passive"))
      (node (ref "U2") (pin "45") (pinfunction "EN_45") (pintype "input"))
    )
    (net (code "50") (name "Net-(U2-IO0)") (class "Default")
      (node (ref "C11") (pin "1") (pinfunction "1_1") (pintype "passive"))
      (node (ref "R3") (pin "1") (pinfunction "1_1") (pintype "passive"))
      (node (ref "SW5") (pin "3") (pinfunction "3_3") (pintype "passive"))
      (node (ref "SW5") (pin "4") (pinfunction "4_4") (pintype "passive"))
      (node (ref "U2") (pin "4") (pinfunction "IO0_4") (pintype "bidirectional"))
    )
    (net (code "51") (name "Net-(U3-DM)") (class "Default")
      (node (ref "U3") (pin "4") (pinfunction "DP_4") (pintype "passive"))
      (node (ref "U3") (pin "5") (pinfunction "DM_5") (pintype "passive"))
    )
    (net (code "52") (name "Net-(U3-VBUS)") (class "Default")
      (node (ref "R19") (pin "2") (pinfunction "2_2") (pintype "passive"))
      (node (ref "U3") (pin "8") (pinfunction "VBUS_8") (pintype "passive"))
    )
    (net (code "53") (name "Net-(U4-EN)") (class "Default")
      (node (ref "R20") (pin "1") (pinfunction "1_1") (pintype "passive"))
      (node (ref "U4") (pin "1") (pinfunction "EN_1") (pintype "passive"))
    )
    (net (code "54") (name "Net-(U4-VOUT_S)") (class "Default")
      (node (ref "R27") (pin "1") (pinfunction "1_1") (pintype "passive"))
      (node (ref "U4") (pin "6") (pinfunction "VOUT_S_6") (pintype "passive"))
    )
    (net (code "55") (name "VBUS") (class "Default")
      (node (ref "C10") (pin "2") (pinfunction "2_2") (pintype "passive"))
      (node (ref "C15") (pin "2") (pinfunction "2_2") (pintype "passive"))
      (node (ref "C16") (pin "1") (pinfunction "1_1") (pintype "passive"))
      (node (ref "C6") (pin "2") (pinfunction "2_2") (pintype "passive"))
      (node (ref "C7") (pin "2") (pinfunction "2_2") (pintype "passive"))
      (node (ref "C8") (pin "1") (pinfunction "1_1") (pintype "passive"))
      (node (ref "J4") (pin "A4_B9") (pinfunction "VBUS_A4_B9") (pintype "power_in"))
      (node (ref "J4") (pin "B4_A9") (pinfunction "VBUS_B4_A9") (pintype "power_in"))
      (node (ref "R11") (pin "2") (pinfunction "2_2") (pintype "passive"))
      (node (ref "R17") (pin "2") (pinfunction "2_2") (pintype "passive"))
      (node (ref "R19") (pin "1") (pinfunction "1_1") (pintype "passive"))
      (node (ref "R20") (pin "2") (pinfunction "2_2") (pintype "passive"))
      (node (ref "U1") (pin "22") (pinfunction "VS_22") (pintype "power_in"))
      (node (ref "U1") (pin "28") (pinfunction "VS_28") (pintype "power_in"))
      (node (ref "U4") (pin "2") (pinfunction "VIN_2") (pintype "power_in"))
    )
    (net (code "56") (name "unconnected-(IC1-OUT-Pad3)") (class "Default")
      (node (ref "IC1") (pin "3") (pinfunction "OUT_3") (pintype "bidirectional+no_connect"))
    )
    (net (code "57") (name "unconnected-(IC1-PGO-Pad5)") (class "Default")
      (node (ref "IC1") (pin "5") (pinfunction "PGO_5") (pintype "bidirectional+no_connect"))
    )
    (net (code "58") (name "unconnected-(J4-SBU1-PadA8)") (class "Default")
      (node (ref "J4") (pin "A8") (pinfunction "SBU1_A8") (pintype "bidirectional+no_connect"))
    )
    (net (code "59") (name "unconnected-(J4-SBU2-PadB8)") (class "Default")
      (node (ref "J4") (pin "B8") (pinfunction "SBU2_B8") (pintype "bidirectional+no_connect"))
    )
    (net (code "60") (name "unconnected-(U1-NC-Pad25)") (class "Default")
      (node (ref "U1") (pin "25") (pinfunction "NC_25") (pintype "passive+no_connect"))
    )
    (net (code "61") (name "unconnected-(U1-STDBY-Pad20)") (class "Default")
      (node (ref "U1") (pin "20") (pinfunction "STDBY_20") (pintype "input+no_connect"))
    )
    (net (code "62") (name "unconnected-(U2-IO3-Pad7)") (class "Default")
      (node (ref "U2") (pin "7") (pinfunction "IO3_7") (pintype "bidirectional+no_connect"))
    )
    (net (code "63") (name "unconnected-(U2-IO26-Pad26)") (class "Default")
      (node (ref "U2") (pin "26") (pinfunction "IO26_26") (pintype "bidirectional+no_connect"))
    )
    (net (code "64") (name "unconnected-(U2-IO33-Pad28)") (class "Default")
      (node (ref "U2") (pin "28") (pinfunction "IO33_28") (pintype "bidirectional+no_connect"))
    )
    (net (code "65") (name "unconnected-(U2-IO34-Pad29)") (class "Default")
      (node (ref "U2") (pin "29") (pinfunction "IO34_29") (pintype "bidirectional+no_connect"))
    )
    (net (code "66") (name "unconnected-(U2-IO39-Pad35)") (class "Default")
      (node (ref "U2") (pin "35") (pinfunction "IO39_35") (pintype "bidirectional+no_connect"))
    )
    (net (code "67") (name "unconnected-(U2-IO40-Pad36)") (class "Default")
      (node (ref "U2") (pin "36") (pinfunction "IO40_36") (pintype "bidirectional+no_connect"))
    )
    (net (code "68") (name "unconnected-(U2-IO41-Pad37)") (class "Default")
      (node (ref "U2") (pin "37") (pinfunction "IO41_37") (pintype "bidirectional+no_connect"))
    )
    (net (code "69") (name "unconnected-(U2-IO42-Pad38)") (class "Default")
      (node (ref "U2") (pin "38") (pinfunction "IO42_38") (pintype "bidirectional+no_connect"))
    )
    (net (code "70") (name "unconnected-(U2-IO45-Pad41)") (class "Default")
      (node (ref "U2") (pin "41") (pinfunction "IO45_41") (pintype "bidirectional+no_connect"))
    )
    (net (code "71") (name "unconnected-(U2-IO46-Pad44)") (class "Default")
      (node (ref "U2") (pin "44") (pinfunction "IO46_44") (pintype "bidirectional+no_connect"))
    )
    (net (code "72") (name "unconnected-(U2-RXD0-Pad40)") (class "Default")
      (node (ref "U2") (pin "40") (pinfunction "RXD0_40") (pintype "bidirectional+no_connect"))
    )
    (net (code "73") (name "unconnected-(U2-TXD0-Pad39)") (class "Default")
      (node (ref "U2") (pin "39") (pinfunction "TXD0_39") (pintype "bidirectional+no_connect"))
    )
    (net (code "74") (name "unconnected-(U4-NC1-Pad9)") (class "Default")
      (node (ref "U4") (pin "9") (pinfunction "NC1_9") (pintype "passive+no_connect"))
    )
    (net (code "75") (name "unconnected-(U4-NC2-Pad10)") (class "Default")
      (node (ref "U4") (pin "10") (pinfunction "NC2_10") (pintype "passive+no_connect"))
    )
    (net (code "76") (name "unconnected-(U4-VCC-Pad8)") (class "Default")
      (node (ref "U4") (pin "8") (pinfunction "VCC_8") (pintype "power_in+no_connect"))
    )
  )
)
